# CrashButtonESP8266test.net
KiCad netlist of a schematic drawn in EAGLE
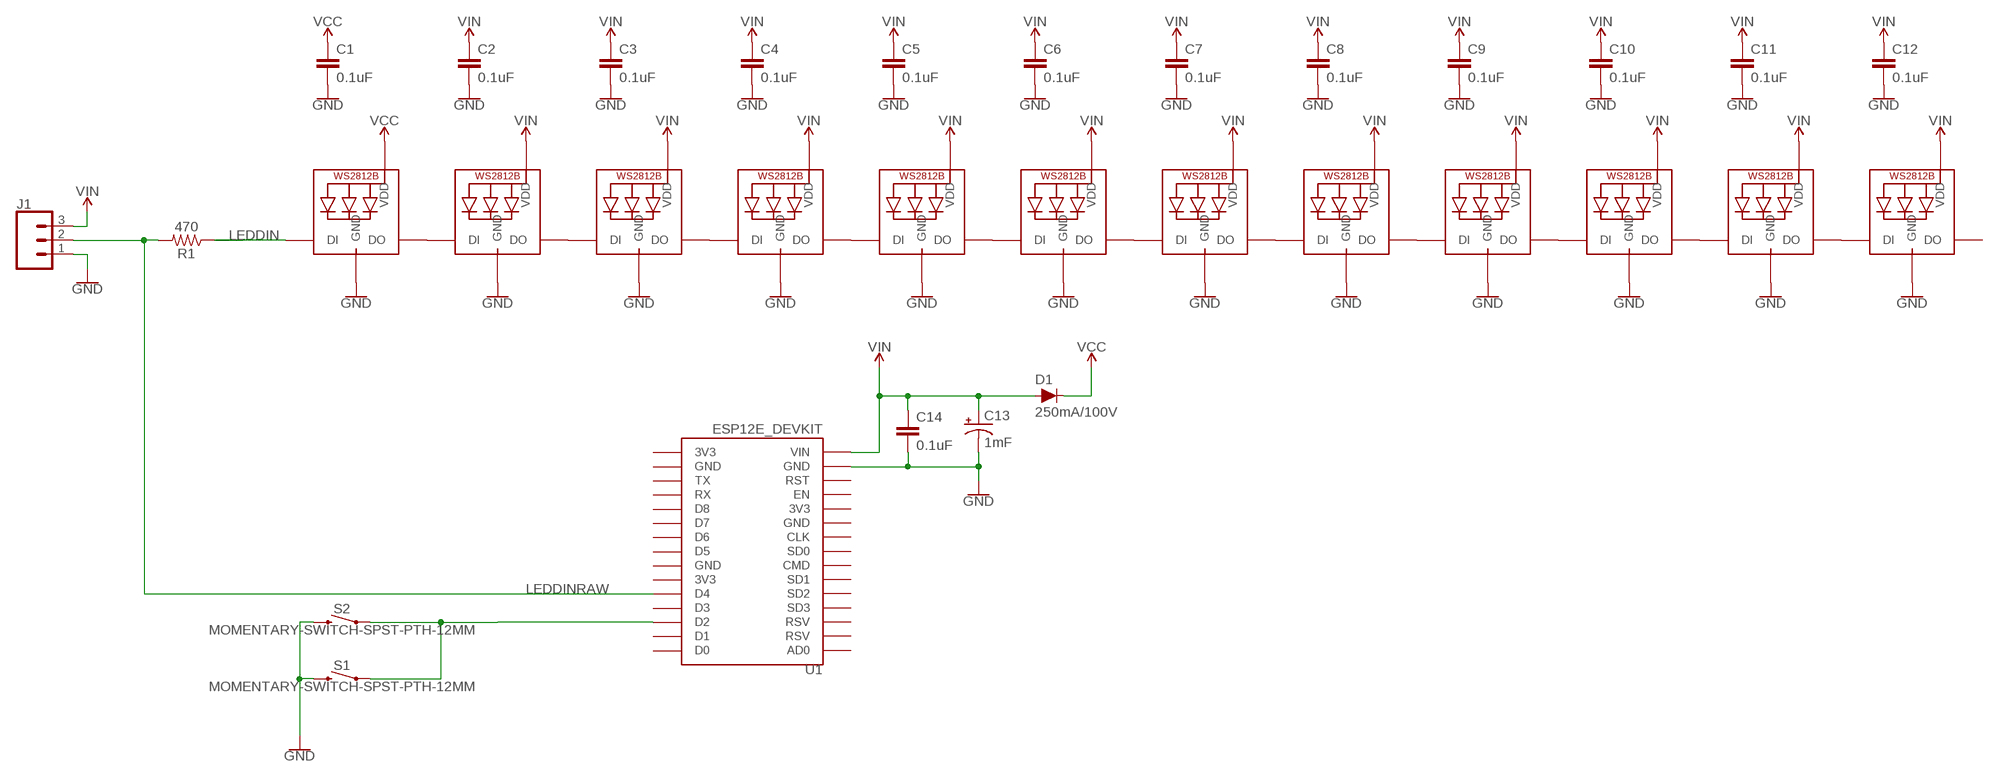
[diagram p0: schematic, sheet 1]

(export (version "E")
  (design (tool "Eeschema 10.0.6"))
  (components
    (comp (ref "C1")
      (value "0.1uF")
      (footprint "eagle-import:0603")
      (libsource (lib "eagle-import") (part "0.1UF-0603-25V-(+80/-20%)"))
    )
    (comp (ref "C2")
      (value "0.1uF")
      (footprint "eagle-import:0603")
      (libsource (lib "eagle-import") (part "0.1UF-0603-25V-(+80/-20%)"))
    )
    (comp (ref "C3")
      (value "0.1uF")
      (footprint "eagle-import:0603")
      (libsource (lib "eagle-import") (part "0.1UF-0603-25V-(+80/-20%)"))
    )
    (comp (ref "C4")
      (value "0.1uF")
      (footprint "eagle-import:0603")
      (libsource (lib "eagle-import") (part "0.1UF-0603-25V-(+80/-20%)"))
    )
    (comp (ref "C5")
      (value "0.1uF")
      (footprint "eagle-import:0603")
      (libsource (lib "eagle-import") (part "0.1UF-0603-25V-(+80/-20%)"))
    )
    (comp (ref "C6")
      (value "0.1uF")
      (footprint "eagle-import:0603")
      (libsource (lib "eagle-import") (part "0.1UF-0603-25V-(+80/-20%)"))
    )
    (comp (ref "C7")
      (value "0.1uF")
      (footprint "eagle-import:0603")
      (libsource (lib "eagle-import") (part "0.1UF-0603-25V-(+80/-20%)"))
    )
    (comp (ref "C8")
      (value "0.1uF")
      (footprint "eagle-import:0603")
      (libsource (lib "eagle-import") (part "0.1UF-0603-25V-(+80/-20%)"))
    )
    (comp (ref "C9")
      (value "0.1uF")
      (footprint "eagle-import:0603")
      (libsource (lib "eagle-import") (part "0.1UF-0603-25V-(+80/-20%)"))
    )
    (comp (ref "C10")
      (value "0.1uF")
      (footprint "eagle-import:0603")
      (libsource (lib "eagle-import") (part "0.1UF-0603-25V-(+80/-20%)"))
    )
    (comp (ref "C11")
      (value "0.1uF")
      (footprint "eagle-import:0603")
      (libsource (lib "eagle-import") (part "0.1UF-0603-25V-(+80/-20%)"))
    )
    (comp (ref "C12")
      (value "0.1uF")
      (footprint "eagle-import:0603")
      (libsource (lib "eagle-import") (part "0.1UF-0603-25V-(+80/-20%)"))
    )
    (comp (ref "C13")
      (value "1mF")
      (footprint "eagle-import:CPOL-RADIAL-5MM-10MM")
      (libsource (lib "eagle-import") (part "1000UF-RADIAL-5MM-25V-20%"))
    )
    (comp (ref "C14")
      (value "0.1uF")
      (footprint "eagle-import:0603")
      (libsource (lib "eagle-import") (part "0.1UF-0603-25V-(+80/-20%)"))
    )
    (comp (ref "D1")
      (value "250mA/100V")
      (footprint "eagle-import:SOD-323")
      (libsource (lib "eagle-import") (part "DIODE-BAS16J"))
    )
    (comp (ref "J1")
      (value "CONN_03")
      (footprint "eagle-import:1X03")
      (libsource (lib "eagle-import") (part "CONN_03"))
    )
    (comp (ref "LED1")
      (value "WS2812B5050")
      (footprint "eagle-import:WS2812B")
      (libsource (lib "eagle-import") (part "WS2812B5050"))
    )
    (comp (ref "LED2")
      (value "WS2812B5050")
      (footprint "eagle-import:WS2812B")
      (libsource (lib "eagle-import") (part "WS2812B5050"))
    )
    (comp (ref "LED3")
      (value "WS2812B5050")
      (footprint "eagle-import:WS2812B")
      (libsource (lib "eagle-import") (part "WS2812B5050"))
    )
    (comp (ref "LED4")
      (value "WS2812B5050")
      (footprint "eagle-import:WS2812B")
      (libsource (lib "eagle-import") (part "WS2812B5050"))
    )
    (comp (ref "LED5")
      (value "WS2812B5050")
      (footprint "eagle-import:WS2812B")
      (libsource (lib "eagle-import") (part "WS2812B5050"))
    )
    (comp (ref "LED6")
      (value "WS2812B5050")
      (footprint "eagle-import:WS2812B")
      (libsource (lib "eagle-import") (part "WS2812B5050"))
    )
    (comp (ref "LED7")
      (value "WS2812B5050")
      (footprint "eagle-import:WS2812B")
      (libsource (lib "eagle-import") (part "WS2812B5050"))
    )
    (comp (ref "LED8")
      (value "WS2812B5050")
      (footprint "eagle-import:WS2812B")
      (libsource (lib "eagle-import") (part "WS2812B5050"))
    )
    (comp (ref "LED9")
      (value "WS2812B5050")
      (footprint "eagle-import:WS2812B")
      (libsource (lib "eagle-import") (part "WS2812B5050"))
    )
    (comp (ref "LED10")
      (value "WS2812B5050")
      (footprint "eagle-import:WS2812B")
      (libsource (lib "eagle-import") (part "WS2812B5050"))
    )
    (comp (ref "LED11")
      (value "WS2812B5050")
      (footprint "eagle-import:WS2812B")
      (libsource (lib "eagle-import") (part "WS2812B5050"))
    )
    (comp (ref "LED12")
      (value "WS2812B5050")
      (footprint "eagle-import:WS2812B")
      (libsource (lib "eagle-import") (part "WS2812B5050"))
    )
    (comp (ref "R1")
      (value "470")
      (footprint "eagle-import:0603")
      (libsource (lib "eagle-import") (part "470OHM-0603-1/10W-1%"))
    )
    (comp (ref "S1")
      (value "MOMENTARY-SWITCH-SPST-PTH-12MM")
      (footprint "eagle-import:TACTILE_SWITCH_PTH_12MM")
      (libsource (lib "eagle-import") (part "MOMENTARY-SWITCH-SPST-PTH-12MM"))
    )
    (comp (ref "S2")
      (value "MOMENTARY-SWITCH-SPST-PTH-12MM")
      (footprint "eagle-import:TACTILE_SWITCH_PTH_12MM")
      (libsource (lib "eagle-import") (part "MOMENTARY-SWITCH-SPST-PTH-12MM"))
    )
    (comp (ref "U1")
      (value "ESP12E_DEVKIT")
      (footprint "eagle-import:ESP12E_DEVKIT")
      (libsource (lib "eagle-import") (part "ESP12E_DEVKIT"))
    )
  )
  (nets
    (net (code "1") (name "/LEDDIN") (class "Default")
      (node (ref "LED1") (pin "4-DIN") (pinfunction "DI_4-DIN") (pintype "input"))
      (node (ref "R1") (pin "1") (pinfunction "1_1") (pintype "passive"))
    )
    (net (code "2") (name "/LEDDINRAW") (class "Default")
      (node (ref "J1") (pin "2") (pinfunction "2_2") (pintype "passive"))
      (node (ref "R1") (pin "2") (pinfunction "2_2") (pintype "passive"))
      (node (ref "U1") (pin "D4") (pinfunction "D4_D4") (pintype "bidirectional"))
    )
    (net (code "3") (name "GND") (class "Default")
      (node (ref "C1") (pin "2") (pinfunction "2_2") (pintype "passive"))
      (node (ref "C10") (pin "2") (pinfunction "2_2") (pintype "passive"))
      (node (ref "C11") (pin "2") (pinfunction "2_2") (pintype "passive"))
      (node (ref "C12") (pin "2") (pinfunction "2_2") (pintype "passive"))
      (node (ref "C13") (pin "-") (pinfunction "-_-") (pintype "passive"))
      (node (ref "C14") (pin "2") (pinfunction "2_2") (pintype "passive"))
      (node (ref "C2") (pin "2") (pinfunction "2_2") (pintype "passive"))
      (node (ref "C3") (pin "2") (pinfunction "2_2") (pintype "passive"))
      (node (ref "C4") (pin "2") (pinfunction "2_2") (pintype "passive"))
      (node (ref "C5") (pin "2") (pinfunction "2_2") (pintype "passive"))
      (node (ref "C6") (pin "2") (pinfunction "2_2") (pintype "passive"))
      (node (ref "C7") (pin "2") (pinfunction "2_2") (pintype "passive"))
      (node (ref "C8") (pin "2") (pinfunction "2_2") (pintype "passive"))
      (node (ref "C9") (pin "2") (pinfunction "2_2") (pintype "passive"))
      (node (ref "J1") (pin "1") (pinfunction "1_1") (pintype "passive"))
      (node (ref "LED1") (pin "3-GND") (pinfunction "GND_3-GND") (pintype "power_in"))
      (node (ref "LED10") (pin "3-GND") (pinfunction "GND_3-GND") (pintype "power_in"))
      (node (ref "LED11") (pin "3-GND") (pinfunction "GND_3-GND") (pintype "power_in"))
      (node (ref "LED12") (pin "3-GND") (pinfunction "GND_3-GND") (pintype "power_in"))
      (node (ref "LED2") (pin "3-GND") (pinfunction "GND_3-GND") (pintype "power_in"))
      (node (ref "LED3") (pin "3-GND") (pinfunction "GND_3-GND") (pintype "power_in"))
      (node (ref "LED4") (pin "3-GND") (pinfunction "GND_3-GND") (pintype "power_in"))
      (node (ref "LED5") (pin "3-GND") (pinfunction "GND_3-GND") (pintype "power_in"))
      (node (ref "LED6") (pin "3-GND") (pinfunction "GND_3-GND") (pintype "power_in"))
      (node (ref "LED7") (pin "3-GND") (pinfunction "GND_3-GND") (pintype "power_in"))
      (node (ref "LED8") (pin "3-GND") (pinfunction "GND_3-GND") (pintype "power_in"))
      (node (ref "LED9") (pin "3-GND") (pinfunction "GND_3-GND") (pintype "power_in"))
      (node (ref "S1") (pin "3") (pinfunction "2_3") (pintype "passive"))
      (node (ref "S2") (pin "3") (pinfunction "2_3") (pintype "passive"))
      (node (ref "U1") (pin "GND@1") (pinfunction "GND_GND@1") (pintype "bidirectional"))
    )
    (net (code "4") (name "Net-(LED1-DO)") (class "Default")
      (node (ref "LED1") (pin "2-DOUT") (pinfunction "DO_2-DOUT") (pintype "output"))
      (node (ref "LED2") (pin "4-DIN") (pinfunction "DI_4-DIN") (pintype "input"))
    )
    (net (code "5") (name "Net-(LED2-DO)") (class "Default")
      (node (ref "LED2") (pin "2-DOUT") (pinfunction "DO_2-DOUT") (pintype "output"))
      (node (ref "LED3") (pin "4-DIN") (pinfunction "DI_4-DIN") (pintype "input"))
    )
    (net (code "6") (name "Net-(LED3-DO)") (class "Default")
      (node (ref "LED3") (pin "2-DOUT") (pinfunction "DO_2-DOUT") (pintype "output"))
      (node (ref "LED4") (pin "4-DIN") (pinfunction "DI_4-DIN") (pintype "input"))
    )
    (net (code "7") (name "Net-(LED4-DO)") (class "Default")
      (node (ref "LED4") (pin "2-DOUT") (pinfunction "DO_2-DOUT") (pintype "output"))
      (node (ref "LED5") (pin "4-DIN") (pinfunction "DI_4-DIN") (pintype "input"))
    )
    (net (code "8") (name "Net-(LED5-DO)") (class "Default")
      (node (ref "LED5") (pin "2-DOUT") (pinfunction "DO_2-DOUT") (pintype "output"))
      (node (ref "LED6") (pin "4-DIN") (pinfunction "DI_4-DIN") (pintype "input"))
    )
    (net (code "9") (name "Net-(LED6-DO)") (class "Default")
      (node (ref "LED6") (pin "2-DOUT") (pinfunction "DO_2-DOUT") (pintype "output"))
      (node (ref "LED7") (pin "4-DIN") (pinfunction "DI_4-DIN") (pintype "input"))
    )
    (net (code "10") (name "Net-(LED7-DO)") (class "Default")
      (node (ref "LED7") (pin "2-DOUT") (pinfunction "DO_2-DOUT") (pintype "output"))
      (node (ref "LED8") (pin "4-DIN") (pinfunction "DI_4-DIN") (pintype "input"))
    )
    (net (code "11") (name "Net-(LED8-DO)") (class "Default")
      (node (ref "LED8") (pin "2-DOUT") (pinfunction "DO_2-DOUT") (pintype "output"))
      (node (ref "LED9") (pin "4-DIN") (pinfunction "DI_4-DIN") (pintype "input"))
    )
    (net (code "12") (name "Net-(LED10-DI)") (class "Default")
      (node (ref "LED10") (pin "4-DIN") (pinfunction "DI_4-DIN") (pintype "input"))
      (node (ref "LED9") (pin "2-DOUT") (pinfunction "DO_2-DOUT") (pintype "output"))
    )
    (net (code "13") (name "Net-(LED10-DO)") (class "Default")
      (node (ref "LED10") (pin "2-DOUT") (pinfunction "DO_2-DOUT") (pintype "output"))
      (node (ref "LED11") (pin "4-DIN") (pinfunction "DI_4-DIN") (pintype "input"))
    )
    (net (code "14") (name "Net-(LED11-DO)") (class "Default")
      (node (ref "LED11") (pin "2-DOUT") (pinfunction "DO_2-DOUT") (pintype "output"))
      (node (ref "LED12") (pin "4-DIN") (pinfunction "DI_4-DIN") (pintype "input"))
    )
    (net (code "15") (name "Net-(S1-Pad1)") (class "Default")
      (node (ref "S1") (pin "1") (pinfunction "1_1") (pintype "passive"))
      (node (ref "S2") (pin "1") (pinfunction "1_1") (pintype "passive"))
      (node (ref "U1") (pin "D2") (pinfunction "D2_D2") (pintype "bidirectional"))
    )
    (net (code "16") (name "VCC") (class "Default")
      (node (ref "C1") (pin "1") (pinfunction "1_1") (pintype "passive"))
      (node (ref "D1") (pin "C") (pinfunction "C_C") (pintype "passive"))
      (node (ref "LED1") (pin "1-VDD") (pinfunction "VDD_1-VDD") (pintype "power_in"))
    )
    (net (code "17") (name "VIN") (class "Default")
      (node (ref "C10") (pin "1") (pinfunction "1_1") (pintype "passive"))
      (node (ref "C11") (pin "1") (pinfunction "1_1") (pintype "passive"))
      (node (ref "C12") (pin "1") (pinfunction "1_1") (pintype "passive"))
      (node (ref "C13") (pin "+") (pinfunction "+_+") (pintype "passive"))
      (node (ref "C14") (pin "1") (pinfunction "1_1") (pintype "passive"))
      (node (ref "C2") (pin "1") (pinfunction "1_1") (pintype "passive"))
      (node (ref "C3") (pin "1") (pinfunction "1_1") (pintype "passive"))
      (node (ref "C4") (pin "1") (pinfunction "1_1") (pintype "passive"))
      (node (ref "C5") (pin "1") (pinfunction "1_1") (pintype "passive"))
      (node (ref "C6") (pin "1") (pinfunction "1_1") (pintype "passive"))
      (node (ref "C7") (pin "1") (pinfunction "1_1") (pintype "passive"))
      (node (ref "C8") (pin "1") (pinfunction "1_1") (pintype "passive"))
      (node (ref "C9") (pin "1") (pinfunction "1_1") (pintype "passive"))
      (node (ref "D1") (pin "A") (pinfunction "A_A") (pintype "passive"))
      (node (ref "J1") (pin "3") (pinfunction "3_3") (pintype "passive"))
      (node (ref "LED10") (pin "1-VDD") (pinfunction "VDD_1-VDD") (pintype "power_in"))
      (node (ref "LED11") (pin "1-VDD") (pinfunction "VDD_1-VDD") (pintype "power_in"))
      (node (ref "LED12") (pin "1-VDD") (pinfunction "VDD_1-VDD") (pintype "power_in"))
      (node (ref "LED2") (pin "1-VDD") (pinfunction "VDD_1-VDD") (pintype "power_in"))
      (node (ref "LED3") (pin "1-VDD") (pinfunction "VDD_1-VDD") (pintype "power_in"))
      (node (ref "LED4") (pin "1-VDD") (pinfunction "VDD_1-VDD") (pintype "power_in"))
      (node (ref "LED5") (pin "1-VDD") (pinfunction "VDD_1-VDD") (pintype "power_in"))
      (node (ref "LED6") (pin "1-VDD") (pinfunction "VDD_1-VDD") (pintype "power_in"))
      (node (ref "LED7") (pin "1-VDD") (pinfunction "VDD_1-VDD") (pintype "power_in"))
      (node (ref "LED8") (pin "1-VDD") (pinfunction "VDD_1-VDD") (pintype "power_in"))
      (node (ref "LED9") (pin "1-VDD") (pinfunction "VDD_1-VDD") (pintype "power_in"))
      (node (ref "U1") (pin "VIN") (pinfunction "VIN_VIN") (pintype "bidirectional"))
    )
    (net (code "18") (name "unconnected-(LED12-DO-Pad2-DOUT)") (class "Default")
      (node (ref "LED12") (pin "2-DOUT") (pinfunction "DO_2-DOUT") (pintype "output"))
    )
    (net (code "19") (name "unconnected-(U1-3V3-Pad3V3@0)") (class "Default")
      (node (ref "U1") (pin "3V3@0") (pinfunction "3V3_3V3@0") (pintype "bidirectional"))
    )
    (net (code "20") (name "unconnected-(U1-3V3-Pad3V3@1)") (class "Default")
      (node (ref "U1") (pin "3V3@1") (pinfunction "3V3_3V3@1") (pintype "bidirectional"))
    )
    (net (code "21") (name "unconnected-(U1-3V3-Pad3V3@2)") (class "Default")
      (node (ref "U1") (pin "3V3@2") (pinfunction "3V3_3V3@2") (pintype "bidirectional"))
    )
    (net (code "22") (name "unconnected-(U1-GND-PadGND@0)") (class "Default")
      (node (ref "U1") (pin "GND@0") (pinfunction "GND_GND@0") (pintype "bidirectional"))
    )
    (net (code "23") (name "unconnected-(U1-GND-PadGND@2)") (class "Default")
      (node (ref "U1") (pin "GND@2") (pinfunction "GND_GND@2") (pintype "bidirectional"))
    )
    (net (code "24") (name "unconnected-(U1-GND-PadGND@3)") (class "Default")
      (node (ref "U1") (pin "GND@3") (pinfunction "GND_GND@3") (pintype "bidirectional"))
    )
    (net (code "25") (name "unconnected-(U1-PadAD0)") (class "Default")
      (node (ref "U1") (pin "AD0") (pinfunction "AD0_AD0") (pintype "bidirectional"))
    )
    (net (code "26") (name "unconnected-(U1-PadCLK)") (class "Default")
      (node (ref "U1") (pin "CLK") (pinfunction "CLK_CLK") (pintype "bidirectional"))
    )
    (net (code "27") (name "unconnected-(U1-PadCMD)") (class "Default")
      (node (ref "U1") (pin "CMD") (pinfunction "CMD_CMD") (pintype "bidirectional"))
    )
    (net (code "28") (name "unconnected-(U1-PadD0)") (class "Default")
      (node (ref "U1") (pin "D0") (pinfunction "D0_D0") (pintype "bidirectional"))
    )
    (net (code "29") (name "unconnected-(U1-PadD1)") (class "Default")
      (node (ref "U1") (pin "D1") (pinfunction "D1_D1") (pintype "bidirectional"))
    )
    (net (code "30") (name "unconnected-(U1-PadD3)") (class "Default")
      (node (ref "U1") (pin "D3") (pinfunction "D3_D3") (pintype "bidirectional"))
    )
    (net (code "31") (name "unconnected-(U1-PadD5)") (class "Default")
      (node (ref "U1") (pin "D5") (pinfunction "D5_D5") (pintype "bidirectional"))
    )
    (net (code "32") (name "unconnected-(U1-PadD6)") (class "Default")
      (node (ref "U1") (pin "D6") (pinfunction "D6_D6") (pintype "bidirectional"))
    )
    (net (code "33") (name "unconnected-(U1-PadD7)") (class "Default")
      (node (ref "U1") (pin "D7") (pinfunction "D7_D7") (pintype "bidirectional"))
    )
    (net (code "34") (name "unconnected-(U1-PadD8)") (class "Default")
      (node (ref "U1") (pin "D8") (pinfunction "D8_D8") (pintype "bidirectional"))
    )
    (net (code "35") (name "unconnected-(U1-PadEN)") (class "Default")
      (node (ref "U1") (pin "EN") (pinfunction "EN_EN") (pintype "bidirectional"))
    )
    (net (code "36") (name "unconnected-(U1-PadRST)") (class "Default")
      (node (ref "U1") (pin "RST") (pinfunction "RST_RST") (pintype "bidirectional"))
    )
    (net (code "37") (name "unconnected-(U1-PadRX)") (class "Default")
      (node (ref "U1") (pin "RX") (pinfunction "RX_RX") (pintype "bidirectional"))
    )
    (net (code "38") (name "unconnected-(U1-PadSD0)") (class "Default")
      (node (ref "U1") (pin "SD0") (pinfunction "SD0_SD0") (pintype "bidirectional"))
    )
    (net (code "39") (name "unconnected-(U1-PadSD1)") (class "Default")
      (node (ref "U1") (pin "SD1") (pinfunction "SD1_SD1") (pintype "bidirectional"))
    )
    (net (code "40") (name "unconnected-(U1-PadSD2)") (class "Default")
      (node (ref "U1") (pin "SD2") (pinfunction "SD2_SD2") (pintype "bidirectional"))
    )
    (net (code "41") (name "unconnected-(U1-PadSD3)") (class "Default")
      (node (ref "U1") (pin "SD3") (pinfunction "SD3_SD3") (pintype "bidirectional"))
    )
    (net (code "42") (name "unconnected-(U1-PadTX)") (class "Default")
      (node (ref "U1") (pin "TX") (pinfunction "TX_TX") (pintype "bidirectional"))
    )
    (net (code "43") (name "unconnected-(U1-RSV-PadRSV@0)") (class "Default")
      (node (ref "U1") (pin "RSV@0") (pinfunction "RSV_RSV@0") (pintype "bidirectional"))
    )
    (net (code "44") (name "unconnected-(U1-RSV-PadRSV@1)") (class "Default")
      (node (ref "U1") (pin "RSV@1") (pinfunction "RSV_RSV@1") (pintype "bidirectional"))
    )
  )
)
